# CP2104.net
KiCad netlist of a schematic drawn in Altium Designer
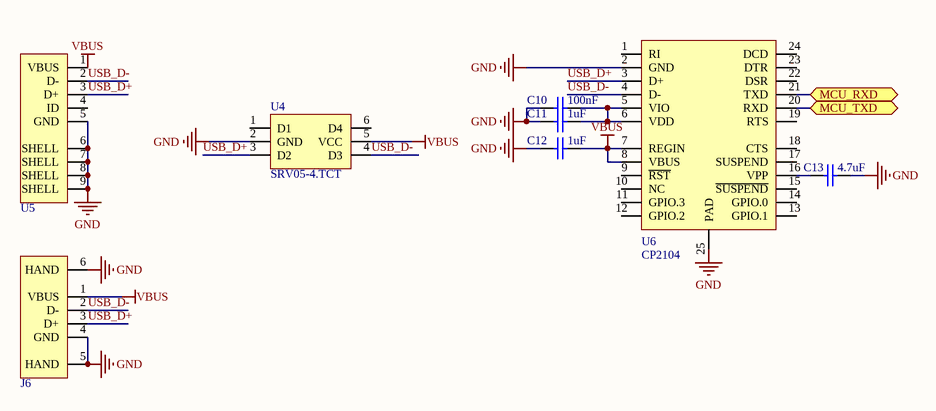
[diagram p0: CP2104.SchDoc]

(export (version "E")
  (design (tool "Eeschema 10.0.6"))
  (components
    (comp (ref "C10")
      (value "100nF")
      (footprint "dq - 0402")
      (description "Capacitor")
      (fields (field (name "Comment") "Cap") (field (name "PUBLISHER") "Altium Limited"))
      (libsource (lib "weifengdq") (part "DQ_Cap"))
    )
    (comp (ref "C11")
      (value "1uF")
      (footprint "dq - 0402")
      (description "Capacitor")
      (fields (field (name "Comment") "Cap") (field (name "PUBLISHER") "Altium Limited"))
      (libsource (lib "weifengdq") (part "DQ_Cap"))
    )
    (comp (ref "C12")
      (value "1uF")
      (footprint "dq - 0402")
      (description "Capacitor")
      (fields (field (name "Comment") "Cap") (field (name "PUBLISHER") "Altium Limited"))
      (libsource (lib "weifengdq") (part "DQ_Cap"))
    )
    (comp (ref "C13")
      (value "4.7uF")
      (footprint "dq - 0603")
      (description "Capacitor")
      (fields (field (name "Comment") "Cap") (field (name "PUBLISHER") "Altium Limited"))
      (libsource (lib "weifengdq") (part "DQ_Cap"))
    )
    (comp (ref "J6")
      (value "USB")
      (footprint "USB-Square-Vertical")
      (libsource (lib "weifengdq") (part "USB"))
    )
    (comp (ref "U4")
      (value "SRV05-4.TCT")
      (footprint "LC-SOT-23-6")
      (libsource (lib "weifengdq") (part "SRV05-4.TCT"))
    )
    (comp (ref "U5")
      (value "Micro-USB-N")
      (footprint "MICRO-USB-F")
      (libsource (lib "weifengdq") (part "Micro-USB-N"))
    )
    (comp (ref "U6") (value "CP2104") (footprint "QFN24 - T") (libsource (lib "weifengdq") (part "CP2104")))
  )
  (nets
    (net (code "1") (name "/MCU_RXD") (class "Default")
      (node (ref "U6") (pin "21") (pinfunction "TXD_21") (pintype "passive"))
    )
    (net (code "2") (name "/MCU_TXD") (class "Default")
      (node (ref "U6") (pin "20") (pinfunction "RXD_20") (pintype "passive"))
    )
    (net (code "3") (name "/USB_D+") (class "Default")
      (node (ref "J6") (pin "3") (pinfunction "D+_3") (pintype "passive"))
      (node (ref "U4") (pin "3") (pinfunction "D2_3") (pintype "passive"))
      (node (ref "U5") (pin "3") (pinfunction "D+_3") (pintype "passive"))
      (node (ref "U6") (pin "3") (pinfunction "D+_3") (pintype "passive"))
    )
    (net (code "4") (name "/USB_D-") (class "Default")
      (node (ref "J6") (pin "2") (pinfunction "D-_2") (pintype "passive"))
      (node (ref "U4") (pin "4") (pinfunction "D3_4") (pintype "passive"))
      (node (ref "U5") (pin "2") (pinfunction "D-_2") (pintype "passive"))
      (node (ref "U6") (pin "4") (pinfunction "D-_4") (pintype "passive"))
    )
    (net (code "5") (name "GND") (class "Default")
      (node (ref "C10") (pin "1") (pinfunction "1_1") (pintype "passive"))
      (node (ref "C11") (pin "1") (pinfunction "1_1") (pintype "passive"))
      (node (ref "C12") (pin "1") (pinfunction "1_1") (pintype "passive"))
      (node (ref "C13") (pin "2") (pinfunction "2_2") (pintype "passive"))
      (node (ref "J6") (pin "4") (pinfunction "GND_4") (pintype "passive"))
      (node (ref "J6") (pin "5") (pinfunction "HAND_5") (pintype "passive"))
      (node (ref "J6") (pin "6") (pinfunction "HAND_6") (pintype "passive"))
      (node (ref "U4") (pin "2") (pinfunction "GND_2") (pintype "passive"))
      (node (ref "U5") (pin "5") (pinfunction "GND_5") (pintype "passive"))
      (node (ref "U5") (pin "6") (pinfunction "SHELL_6") (pintype "passive"))
      (node (ref "U5") (pin "7") (pinfunction "SHELL_7") (pintype "passive"))
      (node (ref "U5") (pin "8") (pinfunction "SHELL_8") (pintype "passive"))
      (node (ref "U5") (pin "9") (pinfunction "SHELL_9") (pintype "passive"))
      (node (ref "U6") (pin "2") (pinfunction "GND_2") (pintype "passive"))
      (node (ref "U6") (pin "25") (pinfunction "PAD_25") (pintype "passive"))
    )
    (net (code "6") (name "Net-(U6-VDD)") (class "Default")
      (node (ref "C10") (pin "2") (pinfunction "2_2") (pintype "passive"))
      (node (ref "C11") (pin "2") (pinfunction "2_2") (pintype "passive"))
      (node (ref "U6") (pin "5") (pinfunction "VIO_5") (pintype "passive"))
      (node (ref "U6") (pin "6") (pinfunction "VDD_6") (pintype "passive"))
    )
    (net (code "7") (name "Net-(U6-VPP)") (class "Default")
      (node (ref "C13") (pin "1") (pinfunction "1_1") (pintype "passive"))
      (node (ref "U6") (pin "16") (pinfunction "VPP_16") (pintype "passive"))
    )
    (net (code "8") (name "VBUS") (class "Default")
      (node (ref "C12") (pin "2") (pinfunction "2_2") (pintype "passive"))
      (node (ref "J6") (pin "1") (pinfunction "VBUS_1") (pintype "passive"))
      (node (ref "U4") (pin "5") (pinfunction "VCC_5") (pintype "passive"))
      (node (ref "U5") (pin "1") (pinfunction "VBUS_1") (pintype "passive"))
      (node (ref "U6") (pin "7") (pinfunction "REGIN_7") (pintype "passive"))
      (node (ref "U6") (pin "8") (pinfunction "VBUS_8") (pintype "passive"))
    )
    (net (code "9") (name "unconnected-(U4-D1-Pad1)") (class "Default")
      (node (ref "U4") (pin "1") (pinfunction "D1_1") (pintype "passive"))
    )
    (net (code "10") (name "unconnected-(U4-D4-Pad6)") (class "Default")
      (node (ref "U4") (pin "6") (pinfunction "D4_6") (pintype "passive"))
    )
    (net (code "11") (name "unconnected-(U5-ID-Pad4)") (class "Default")
      (node (ref "U5") (pin "4") (pinfunction "ID_4") (pintype "passive"))
    )
    (net (code "12") (name "unconnected-(U6-CTS-Pad18)") (class "Default")
      (node (ref "U6") (pin "18") (pinfunction "CTS_18") (pintype "passive"))
    )
    (net (code "13") (name "unconnected-(U6-DCD-Pad24)") (class "Default")
      (node (ref "U6") (pin "24") (pinfunction "DCD_24") (pintype "passive"))
    )
    (net (code "14") (name "unconnected-(U6-DSR-Pad22)") (class "Default")
      (node (ref "U6") (pin "22") (pinfunction "DSR_22") (pintype "passive"))
    )
    (net (code "15") (name "unconnected-(U6-DTR-Pad23)") (class "Default")
      (node (ref "U6") (pin "23") (pinfunction "DTR_23") (pintype "passive"))
    )
    (net (code "16") (name "unconnected-(U6-GPIO.0-Pad14)") (class "Default")
      (node (ref "U6") (pin "14") (pinfunction "GPIO.0_14") (pintype "passive"))
    )
    (net (code "17") (name "unconnected-(U6-GPIO.1-Pad13)") (class "Default")
      (node (ref "U6") (pin "13") (pinfunction "GPIO.1_13") (pintype "passive"))
    )
    (net (code "18") (name "unconnected-(U6-GPIO.2-Pad12)") (class "Default")
      (node (ref "U6") (pin "12") (pinfunction "GPIO.2_12") (pintype "passive"))
    )
    (net (code "19") (name "unconnected-(U6-GPIO.3-Pad11)") (class "Default")
      (node (ref "U6") (pin "11") (pinfunction "GPIO.3_11") (pintype "passive"))
    )
    (net (code "20") (name "unconnected-(U6-NC-Pad10)") (class "Default")
      (node (ref "U6") (pin "10") (pinfunction "NC_10") (pintype "passive"))
    )
    (net (code "21") (name "unconnected-(U6-RI-Pad1)") (class "Default")
      (node (ref "U6") (pin "1") (pinfunction "RI_1") (pintype "passive"))
    )
    (net (code "22") (name "unconnected-(U6-RTS-Pad19)") (class "Default")
      (node (ref "U6") (pin "19") (pinfunction "RTS_19") (pintype "passive"))
    )
    (net (code "23") (name "unconnected-(U6-SUSPEND-Pad17)") (class "Default")
      (node (ref "U6") (pin "17") (pinfunction "SUSPEND_17") (pintype "passive"))
    )
    (net (code "24") (name "unconnected-(U6-~{RST}-Pad9)") (class "Default")
      (node (ref "U6") (pin "9") (pinfunction "~{RST}_9") (pintype "passive"))
    )
    (net (code "25") (name "unconnected-(U6-~{SUSPEND}-Pad15)") (class "Default")
      (node (ref "U6") (pin "15") (pinfunction "~{SUSPEND}_15") (pintype "passive"))
    )
  )
)
